# 433MHz-Sender.net
KiCad netlist of a schematic drawn in EAGLE
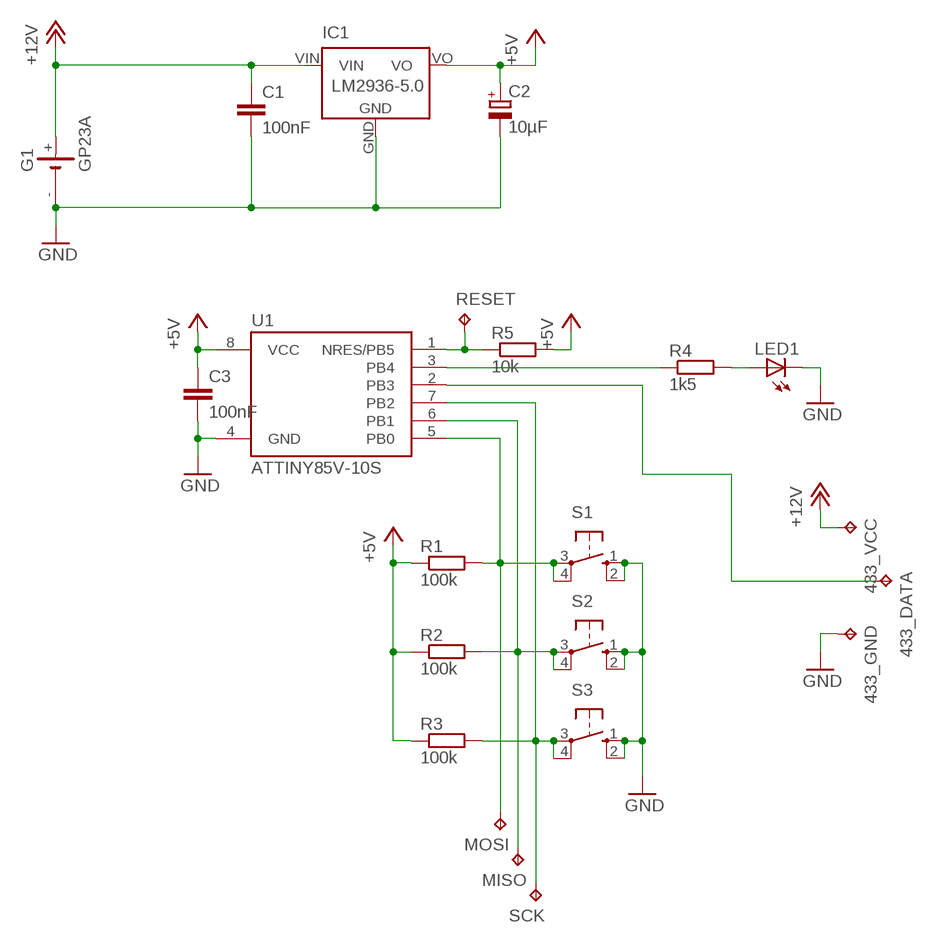
[diagram p0: schematic, sheet 1]

(export (version "E")
  (design (tool "Eeschema 10.0.6"))
  (components
    (comp (ref "433_DATA")
      (value "TPPAD1-13")
      (footprint "eagle-import:P1-13")
      (libsource (lib "eagle-import") (part "TPPAD1-13"))
    )
    (comp (ref "433_GND")
      (value "TPPAD1-13")
      (footprint "eagle-import:P1-13")
      (libsource (lib "eagle-import") (part "TPPAD1-13"))
    )
    (comp (ref "433_VCC")
      (value "TPPAD1-13")
      (footprint "eagle-import:P1-13")
      (libsource (lib "eagle-import") (part "TPPAD1-13"))
    )
    (comp (ref "C1")
      (value "100nF")
      (footprint "eagle-import:C025-025X050")
      (libsource (lib "eagle-import") (part "C-EU025-025X050"))
    )
    (comp (ref "C2")
      (value "10µF")
      (footprint "eagle-import:E2-4")
      (libsource (lib "eagle-import") (part "CPOL-EUE2-4"))
    )
    (comp (ref "C3")
      (value "100nF")
      (footprint "eagle-import:C025-025X050")
      (libsource (lib "eagle-import") (part "C-EU025-025X050"))
    )
    (comp (ref "G1")
      (value "GP23A")
      (footprint "eagle-import:GP23A")
      (libsource (lib "eagle-import") (part "GP23A"))
    )
    (comp (ref "IC1")
      (value "LM2936-5.0")
      (footprint "eagle-import:TO92-INLINE")
      (libsource (lib "eagle-import") (part "LM2936?-5.0"))
    )
    (comp (ref "LED1")
      (value "LED3MM")
      (footprint "eagle-import:LED3MM")
      (libsource (lib "eagle-import") (part "LED3MM"))
    )
    (comp (ref "MISO")
      (value "TPPAD1-13")
      (footprint "eagle-import:P1-13")
      (libsource (lib "eagle-import") (part "TPPAD1-13"))
    )
    (comp (ref "MOSI")
      (value "TPPAD1-13")
      (footprint "eagle-import:P1-13")
      (libsource (lib "eagle-import") (part "TPPAD1-13"))
    )
    (comp (ref "R1")
      (value "100k")
      (footprint "eagle-import:0204_5")
      (libsource (lib "eagle-import") (part "R-EU_0204/5"))
    )
    (comp (ref "R2")
      (value "100k")
      (footprint "eagle-import:0204_5")
      (libsource (lib "eagle-import") (part "R-EU_0204/5"))
    )
    (comp (ref "R3")
      (value "100k")
      (footprint "eagle-import:0204_5")
      (libsource (lib "eagle-import") (part "R-EU_0204/5"))
    )
    (comp (ref "R4")
      (value "1k5")
      (footprint "eagle-import:0204_5")
      (libsource (lib "eagle-import") (part "R-EU_0204/5"))
    )
    (comp (ref "R5")
      (value "10k")
      (footprint "eagle-import:0204_5")
      (libsource (lib "eagle-import") (part "R-EU_0204/5"))
    )
    (comp (ref "RESET")
      (value "TPPAD1-13")
      (footprint "eagle-import:P1-13")
      (libsource (lib "eagle-import") (part "TPPAD1-13"))
    )
    (comp (ref "S1")
      (value "10-XX")
      (footprint "eagle-import:B3F-10XX")
      (fields (field (name "MPN") "B3F-1000"))
      (libsource (lib "eagle-import") (part "10-XX"))
    )
    (comp (ref "S2")
      (value "10-XX")
      (footprint "eagle-import:B3F-10XX")
      (fields (field (name "MPN") "B3F-1000"))
      (libsource (lib "eagle-import") (part "10-XX"))
    )
    (comp (ref "S3")
      (value "10-XX")
      (footprint "eagle-import:B3F-10XX")
      (fields (field (name "MPN") "B3F-1000"))
      (libsource (lib "eagle-import") (part "10-XX"))
    )
    (comp (ref "SCK")
      (value "TPPAD1-13")
      (footprint "eagle-import:P1-13")
      (libsource (lib "eagle-import") (part "TPPAD1-13"))
    )
    (comp (ref "U1")
      (value "ATTINY85V-10S")
      (footprint "eagle-import:SOIC8_EIAJ_208MIL")
      (libsource (lib "eagle-import") (part "ATTINY85SV-10"))
    )
  )
  (nets
    (net (code "1") (name "+5V") (class "Default")
      (node (ref "C2") (pin "+") (pinfunction "+_+") (pintype "passive"))
      (node (ref "C3") (pin "1") (pinfunction "1_1") (pintype "passive"))
      (node (ref "IC1") (pin "VO") (pinfunction "VO_VO") (pintype "passive"))
      (node (ref "R1") (pin "1") (pinfunction "1_1") (pintype "passive"))
      (node (ref "R2") (pin "1") (pinfunction "1_1") (pintype "passive"))
      (node (ref "R3") (pin "1") (pinfunction "1_1") (pintype "passive"))
      (node (ref "R5") (pin "2") (pinfunction "2_2") (pintype "passive"))
      (node (ref "U1") (pin "8") (pinfunction "VCC_8") (pintype "power_in"))
    )
    (net (code "2") (name "+12V") (class "Default")
      (node (ref "433_VCC") (pin "TP") (pinfunction "TP_TP") (pintype "input"))
      (node (ref "C1") (pin "1") (pinfunction "1_1") (pintype "passive"))
      (node (ref "G1") (pin "+") (pinfunction "+_+") (pintype "passive"))
      (node (ref "IC1") (pin "VIN") (pinfunction "VIN_VIN") (pintype "input"))
    )
    (net (code "3") (name "GND") (class "Default")
      (node (ref "433_GND") (pin "TP") (pinfunction "TP_TP") (pintype "input"))
      (node (ref "C1") (pin "2") (pinfunction "2_2") (pintype "passive"))
      (node (ref "C2") (pin "-") (pinfunction "-_-") (pintype "passive"))
      (node (ref "C3") (pin "2") (pinfunction "2_2") (pintype "passive"))
      (node (ref "G1") (pin "-") (pinfunction "-_-") (pintype "passive"))
      (node (ref "IC1") (pin "GND") (pinfunction "GND_GND") (pintype "passive"))
      (node (ref "LED1") (pin "K") (pinfunction "C_K") (pintype "passive"))
      (node (ref "S1") (pin "1") (pinfunction "S_1") (pintype "passive"))
      (node (ref "S1") (pin "2") (pinfunction "S1_2") (pintype "passive"))
      (node (ref "S2") (pin "1") (pinfunction "S_1") (pintype "passive"))
      (node (ref "S2") (pin "2") (pinfunction "S1_2") (pintype "passive"))
      (node (ref "S3") (pin "1") (pinfunction "S_1") (pintype "passive"))
      (node (ref "S3") (pin "2") (pinfunction "S1_2") (pintype "passive"))
      (node (ref "U1") (pin "4") (pinfunction "GND_4") (pintype "power_in"))
    )
    (net (code "4") (name "Net-(LED1-PadA)") (class "Default")
      (node (ref "LED1") (pin "A") (pinfunction "A_A") (pintype "passive"))
      (node (ref "R4") (pin "2") (pinfunction "2_2") (pintype "passive"))
    )
    (net (code "5") (name "Net-(S1-P)") (class "Default")
      (node (ref "MOSI") (pin "TP") (pinfunction "TP_TP") (pintype "input"))
      (node (ref "R1") (pin "2") (pinfunction "2_2") (pintype "passive"))
      (node (ref "S1") (pin "3") (pinfunction "P_3") (pintype "passive"))
      (node (ref "S1") (pin "4") (pinfunction "P1_4") (pintype "passive"))
      (node (ref "U1") (pin "5") (pinfunction "PB0_5") (pintype "bidirectional"))
    )
    (net (code "6") (name "Net-(S2-P)") (class "Default")
      (node (ref "MISO") (pin "TP") (pinfunction "TP_TP") (pintype "input"))
      (node (ref "R2") (pin "2") (pinfunction "2_2") (pintype "passive"))
      (node (ref "S2") (pin "3") (pinfunction "P_3") (pintype "passive"))
      (node (ref "S2") (pin "4") (pinfunction "P1_4") (pintype "passive"))
      (node (ref "U1") (pin "6") (pinfunction "PB1_6") (pintype "bidirectional"))
    )
    (net (code "7") (name "Net-(S3-P)") (class "Default")
      (node (ref "R3") (pin "2") (pinfunction "2_2") (pintype "passive"))
      (node (ref "S3") (pin "3") (pinfunction "P_3") (pintype "passive"))
      (node (ref "S3") (pin "4") (pinfunction "P1_4") (pintype "passive"))
      (node (ref "SCK") (pin "TP") (pinfunction "TP_TP") (pintype "input"))
      (node (ref "U1") (pin "7") (pinfunction "PB2_7") (pintype "bidirectional"))
    )
    (net (code "8") (name "Net-(U1-NRES{slash}PB5)") (class "Default")
      (node (ref "R5") (pin "1") (pinfunction "1_1") (pintype "passive"))
      (node (ref "RESET") (pin "TP") (pinfunction "TP_TP") (pintype "input"))
      (node (ref "U1") (pin "1") (pinfunction "NRES/PB5_1") (pintype "bidirectional"))
    )
    (net (code "9") (name "Net-(U1-PB3)") (class "Default")
      (node (ref "433_DATA") (pin "TP") (pinfunction "TP_TP") (pintype "input"))
      (node (ref "U1") (pin "2") (pinfunction "PB3_2") (pintype "bidirectional"))
    )
    (net (code "10") (name "Net-(U1-PB4)") (class "Default")
      (node (ref "R4") (pin "1") (pinfunction "1_1") (pintype "passive"))
      (node (ref "U1") (pin "3") (pinfunction "PB4_3") (pintype "bidirectional"))
    )
  )
)
